# DA6.net
KiCad netlist of a schematic drawn in EAGLE
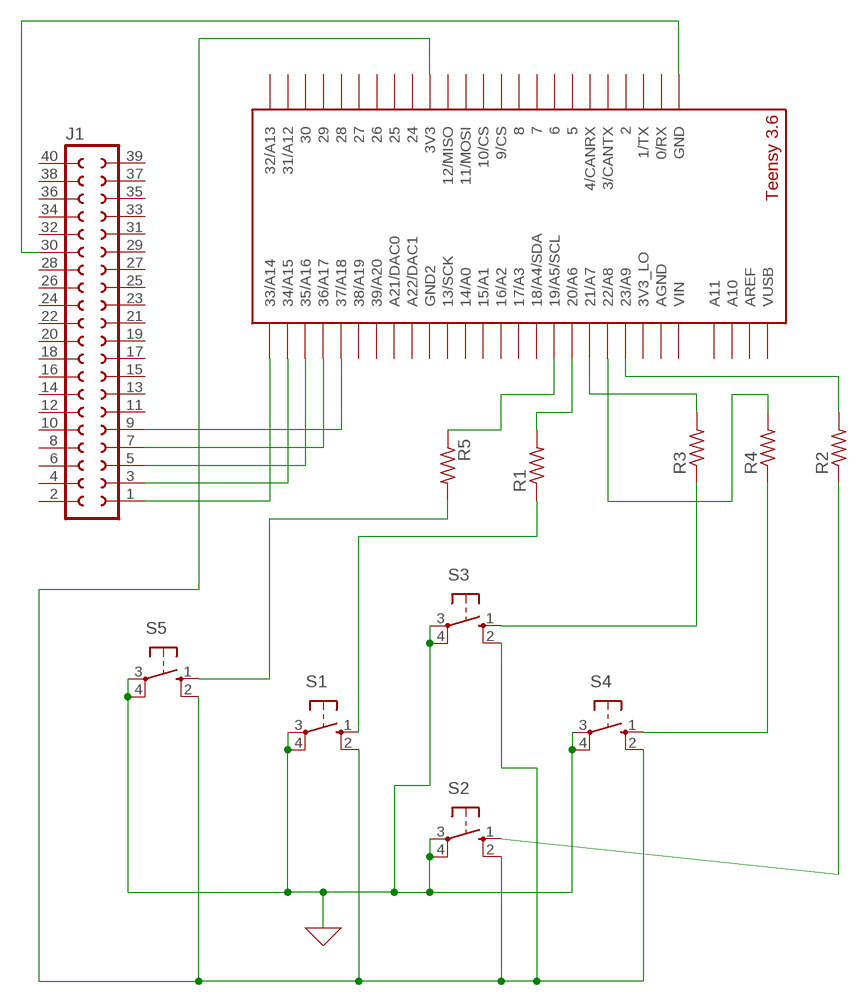
[diagram p0: schematic, sheet 1]

(export (version "E")
  (design (tool "Eeschema 10.0.6"))
  (components
    (comp (ref "J1")
      (value "SOCKET-40V")
      (footprint "eagle-import:S40V")
      (libsource (lib "eagle-import") (part "SOCKET-40V"))
    )
    (comp (ref "R1")
      (value "R-US_0204/2V")
      (footprint "eagle-import:0204V")
      (libsource (lib "eagle-import") (part "R-US_0204/2V"))
    )
    (comp (ref "R2")
      (value "R-US_0204/2V")
      (footprint "eagle-import:0204V")
      (libsource (lib "eagle-import") (part "R-US_0204/2V"))
    )
    (comp (ref "R3")
      (value "R-US_0204/2V")
      (footprint "eagle-import:0204V")
      (libsource (lib "eagle-import") (part "R-US_0204/2V"))
    )
    (comp (ref "R4")
      (value "R-US_0204/2V")
      (footprint "eagle-import:0204V")
      (libsource (lib "eagle-import") (part "R-US_0204/2V"))
    )
    (comp (ref "R5")
      (value "R-US_0204/2V")
      (footprint "eagle-import:0204V")
      (libsource (lib "eagle-import") (part "R-US_0204/2V"))
    )
    (comp (ref "S1")
      (value "10-XX")
      (footprint "eagle-import:B3F-10XX")
      (fields (field (name "MPN") "B3F-1000"))
      (libsource (lib "eagle-import") (part "10-XX"))
    )
    (comp (ref "S2")
      (value "10-XX")
      (footprint "eagle-import:B3F-10XX")
      (fields (field (name "MPN") "B3F-1000"))
      (libsource (lib "eagle-import") (part "10-XX"))
    )
    (comp (ref "S3")
      (value "10-XX")
      (footprint "eagle-import:B3F-10XX")
      (fields (field (name "MPN") "B3F-1000"))
      (libsource (lib "eagle-import") (part "10-XX"))
    )
    (comp (ref "S4")
      (value "10-XX")
      (footprint "eagle-import:B3F-10XX")
      (fields (field (name "MPN") "B3F-1000"))
      (libsource (lib "eagle-import") (part "10-XX"))
    )
    (comp (ref "S5")
      (value "10-XX")
      (footprint "eagle-import:B3F-10XX")
      (fields (field (name "MPN") "B3F-1000"))
      (libsource (lib "eagle-import") (part "10-XX"))
    )
    (comp (ref "U$1")
      (value "TEENSY_3.5/3.6_BASIC")
      (footprint "eagle-import:TEENSY_3.5_3.6_BASIC")
      (libsource (lib "eagle-import") (part "TEENSY_3.5/3.6_BASIC"))
    )
  )
  (nets
    (net (code "1") (name "GND") (class "Default")
      (node (ref "S1") (pin "3") (pinfunction "P_3") (pintype "passive"))
      (node (ref "S1") (pin "4") (pinfunction "P1_4") (pintype "passive"))
      (node (ref "S2") (pin "3") (pinfunction "P_3") (pintype "passive"))
      (node (ref "S2") (pin "4") (pinfunction "P1_4") (pintype "passive"))
      (node (ref "S3") (pin "3") (pinfunction "P_3") (pintype "passive"))
      (node (ref "S3") (pin "4") (pinfunction "P1_4") (pintype "passive"))
      (node (ref "S4") (pin "3") (pinfunction "P_3") (pintype "passive"))
      (node (ref "S4") (pin "4") (pinfunction "P1_4") (pintype "passive"))
      (node (ref "S5") (pin "3") (pinfunction "P_3") (pintype "passive"))
      (node (ref "S5") (pin "4") (pinfunction "P1_4") (pintype "passive"))
    )
    (net (code "2") (name "Net-(J1-Pad1)") (class "Default")
      (node (ref "J1") (pin "1") (pinfunction "1_1") (pintype "passive"))
      (node (ref "U$1") (pin "33/A14") (pinfunction "33/A14_33/A14") (pintype "bidirectional"))
    )
    (net (code "3") (name "Net-(J1-Pad3)") (class "Default")
      (node (ref "J1") (pin "3") (pinfunction "3_3") (pintype "passive"))
      (node (ref "U$1") (pin "34/A15") (pinfunction "34/A15_34/A15") (pintype "bidirectional"))
    )
    (net (code "4") (name "Net-(J1-Pad5)") (class "Default")
      (node (ref "J1") (pin "5") (pinfunction "5_5") (pintype "passive"))
      (node (ref "U$1") (pin "35/A16") (pinfunction "35/A16_35/A16") (pintype "bidirectional"))
    )
    (net (code "5") (name "Net-(J1-Pad7)") (class "Default")
      (node (ref "J1") (pin "7") (pinfunction "7_7") (pintype "passive"))
      (node (ref "U$1") (pin "36/A17") (pinfunction "36/A17_36/A17") (pintype "bidirectional"))
    )
    (net (code "6") (name "Net-(J1-Pad9)") (class "Default")
      (node (ref "J1") (pin "9") (pinfunction "9_9") (pintype "passive"))
      (node (ref "U$1") (pin "37/A18") (pinfunction "37/A18_37/A18") (pintype "bidirectional"))
    )
    (net (code "7") (name "Net-(J1-Pad30)") (class "Default")
      (node (ref "J1") (pin "30") (pinfunction "30_30") (pintype "passive"))
      (node (ref "U$1") (pin "GND") (pinfunction "GND_GND") (pintype "bidirectional"))
    )
    (net (code "8") (name "Net-(R1-Pad2)") (class "Default")
      (node (ref "R1") (pin "2") (pinfunction "2_2") (pintype "passive"))
      (node (ref "U$1") (pin "20/A6") (pinfunction "20/A6_20/A6") (pintype "bidirectional"))
    )
    (net (code "9") (name "Net-(R2-Pad2)") (class "Default")
      (node (ref "R2") (pin "2") (pinfunction "2_2") (pintype "passive"))
      (node (ref "U$1") (pin "23/A9") (pinfunction "23/A9_23/A9") (pintype "bidirectional"))
    )
    (net (code "10") (name "Net-(R3-Pad2)") (class "Default")
      (node (ref "R3") (pin "2") (pinfunction "2_2") (pintype "passive"))
      (node (ref "U$1") (pin "21/A7") (pinfunction "21/A7_21/A7") (pintype "bidirectional"))
    )
    (net (code "11") (name "Net-(R4-Pad2)") (class "Default")
      (node (ref "R4") (pin "2") (pinfunction "2_2") (pintype "passive"))
      (node (ref "U$1") (pin "22/A8") (pinfunction "22/A8_22/A8") (pintype "bidirectional"))
    )
    (net (code "12") (name "Net-(R5-Pad1)") (class "Default")
      (node (ref "R5") (pin "1") (pinfunction "1_1") (pintype "passive"))
      (node (ref "U$1") (pin "19/A5/SCL") (pinfunction "19/A5/SCL_19/A5/SCL") (pintype "bidirectional"))
    )
    (net (code "13") (name "Net-(S1-S)") (class "Default")
      (node (ref "R1") (pin "1") (pinfunction "1_1") (pintype "passive"))
      (node (ref "S1") (pin "1") (pinfunction "S_1") (pintype "passive"))
    )
    (net (code "14") (name "Net-(S1-S1)") (class "Default")
      (node (ref "S1") (pin "2") (pinfunction "S1_2") (pintype "passive"))
      (node (ref "S2") (pin "2") (pinfunction "S1_2") (pintype "passive"))
      (node (ref "S3") (pin "2") (pinfunction "S1_2") (pintype "passive"))
      (node (ref "S4") (pin "2") (pinfunction "S1_2") (pintype "passive"))
      (node (ref "S5") (pin "2") (pinfunction "S1_2") (pintype "passive"))
      (node (ref "U$1") (pin "3V3") (pinfunction "3V3_3V3") (pintype "bidirectional"))
    )
    (net (code "15") (name "Net-(S2-S)") (class "Default")
      (node (ref "R2") (pin "1") (pinfunction "1_1") (pintype "passive"))
      (node (ref "S2") (pin "1") (pinfunction "S_1") (pintype "passive"))
    )
    (net (code "16") (name "Net-(S3-S)") (class "Default")
      (node (ref "R3") (pin "1") (pinfunction "1_1") (pintype "passive"))
      (node (ref "S3") (pin "1") (pinfunction "S_1") (pintype "passive"))
    )
    (net (code "17") (name "Net-(S4-S)") (class "Default")
      (node (ref "R4") (pin "1") (pinfunction "1_1") (pintype "passive"))
      (node (ref "S4") (pin "1") (pinfunction "S_1") (pintype "passive"))
    )
    (net (code "18") (name "Net-(S5-S)") (class "Default")
      (node (ref "R5") (pin "2") (pinfunction "2_2") (pintype "passive"))
      (node (ref "S5") (pin "1") (pinfunction "S_1") (pintype "passive"))
    )
    (net (code "19") (name "unconnected-(J1-Pad2)") (class "Default")
      (node (ref "J1") (pin "2") (pinfunction "2_2") (pintype "passive"))
    )
    (net (code "20") (name "unconnected-(J1-Pad4)") (class "Default")
      (node (ref "J1") (pin "4") (pinfunction "4_4") (pintype "passive"))
    )
    (net (code "21") (name "unconnected-(J1-Pad6)") (class "Default")
      (node (ref "J1") (pin "6") (pinfunction "6_6") (pintype "passive"))
    )
    (net (code "22") (name "unconnected-(J1-Pad8)") (class "Default")
      (node (ref "J1") (pin "8") (pinfunction "8_8") (pintype "passive"))
    )
    (net (code "23") (name "unconnected-(J1-Pad10)") (class "Default")
      (node (ref "J1") (pin "10") (pinfunction "10_10") (pintype "passive"))
    )
    (net (code "24") (name "unconnected-(J1-Pad11)") (class "Default")
      (node (ref "J1") (pin "11") (pinfunction "11_11") (pintype "passive"))
    )
    (net (code "25") (name "unconnected-(J1-Pad12)") (class "Default")
      (node (ref "J1") (pin "12") (pinfunction "12_12") (pintype "passive"))
    )
    (net (code "26") (name "unconnected-(J1-Pad13)") (class "Default")
      (node (ref "J1") (pin "13") (pinfunction "13_13") (pintype "passive"))
    )
    (net (code "27") (name "unconnected-(J1-Pad14)") (class "Default")
      (node (ref "J1") (pin "14") (pinfunction "14_14") (pintype "passive"))
    )
    (net (code "28") (name "unconnected-(J1-Pad15)") (class "Default")
      (node (ref "J1") (pin "15") (pinfunction "15_15") (pintype "passive"))
    )
    (net (code "29") (name "unconnected-(J1-Pad16)") (class "Default")
      (node (ref "J1") (pin "16") (pinfunction "16_16") (pintype "passive"))
    )
    (net (code "30") (name "unconnected-(J1-Pad17)") (class "Default")
      (node (ref "J1") (pin "17") (pinfunction "17_17") (pintype "passive"))
    )
    (net (code "31") (name "unconnected-(J1-Pad18)") (class "Default")
      (node (ref "J1") (pin "18") (pinfunction "18_18") (pintype "passive"))
    )
    (net (code "32") (name "unconnected-(J1-Pad19)") (class "Default")
      (node (ref "J1") (pin "19") (pinfunction "19_19") (pintype "passive"))
    )
    (net (code "33") (name "unconnected-(J1-Pad20)") (class "Default")
      (node (ref "J1") (pin "20") (pinfunction "20_20") (pintype "passive"))
    )
    (net (code "34") (name "unconnected-(J1-Pad21)") (class "Default")
      (node (ref "J1") (pin "21") (pinfunction "21_21") (pintype "passive"))
    )
    (net (code "35") (name "unconnected-(J1-Pad22)") (class "Default")
      (node (ref "J1") (pin "22") (pinfunction "22_22") (pintype "passive"))
    )
    (net (code "36") (name "unconnected-(J1-Pad23)") (class "Default")
      (node (ref "J1") (pin "23") (pinfunction "23_23") (pintype "passive"))
    )
    (net (code "37") (name "unconnected-(J1-Pad24)") (class "Default")
      (node (ref "J1") (pin "24") (pinfunction "24_24") (pintype "passive"))
    )
    (net (code "38") (name "unconnected-(J1-Pad25)") (class "Default")
      (node (ref "J1") (pin "25") (pinfunction "25_25") (pintype "passive"))
    )
    (net (code "39") (name "unconnected-(J1-Pad26)") (class "Default")
      (node (ref "J1") (pin "26") (pinfunction "26_26") (pintype "passive"))
    )
    (net (code "40") (name "unconnected-(J1-Pad27)") (class "Default")
      (node (ref "J1") (pin "27") (pinfunction "27_27") (pintype "passive"))
    )
    (net (code "41") (name "unconnected-(J1-Pad28)") (class "Default")
      (node (ref "J1") (pin "28") (pinfunction "28_28") (pintype "passive"))
    )
    (net (code "42") (name "unconnected-(J1-Pad29)") (class "Default")
      (node (ref "J1") (pin "29") (pinfunction "29_29") (pintype "passive"))
    )
    (net (code "43") (name "unconnected-(J1-Pad31)") (class "Default")
      (node (ref "J1") (pin "31") (pinfunction "31_31") (pintype "passive"))
    )
    (net (code "44") (name "unconnected-(J1-Pad32)") (class "Default")
      (node (ref "J1") (pin "32") (pinfunction "32_32") (pintype "passive"))
    )
    (net (code "45") (name "unconnected-(J1-Pad33)") (class "Default")
      (node (ref "J1") (pin "33") (pinfunction "33_33") (pintype "passive"))
    )
    (net (code "46") (name "unconnected-(J1-Pad34)") (class "Default")
      (node (ref "J1") (pin "34") (pinfunction "34_34") (pintype "passive"))
    )
    (net (code "47") (name "unconnected-(J1-Pad35)") (class "Default")
      (node (ref "J1") (pin "35") (pinfunction "35_35") (pintype "passive"))
    )
    (net (code "48") (name "unconnected-(J1-Pad36)") (class "Default")
      (node (ref "J1") (pin "36") (pinfunction "36_36") (pintype "passive"))
    )
    (net (code "49") (name "unconnected-(J1-Pad37)") (class "Default")
      (node (ref "J1") (pin "37") (pinfunction "37_37") (pintype "passive"))
    )
    (net (code "50") (name "unconnected-(J1-Pad38)") (class "Default")
      (node (ref "J1") (pin "38") (pinfunction "38_38") (pintype "passive"))
    )
    (net (code "51") (name "unconnected-(J1-Pad39)") (class "Default")
      (node (ref "J1") (pin "39") (pinfunction "39_39") (pintype "passive"))
    )
    (net (code "52") (name "unconnected-(J1-Pad40)") (class "Default")
      (node (ref "J1") (pin "40") (pinfunction "40_40") (pintype "passive"))
    )
    (net (code "53") (name "unconnected-(U$1-A21{slash}DAC0-Pad21{slash}DAC0)") (class "Default")
      (node (ref "U$1") (pin "21/DAC0") (pinfunction "A21/DAC0_21/DAC0") (pintype "bidirectional"))
    )
    (net (code "54") (name "unconnected-(U$1-Pad0{slash}RX)") (class "Default")
      (node (ref "U$1") (pin "0/RX") (pinfunction "0/RX_0/RX") (pintype "bidirectional"))
    )
    (net (code "55") (name "unconnected-(U$1-Pad1{slash}TX)") (class "Default")
      (node (ref "U$1") (pin "1/TX") (pinfunction "1/TX_1/TX") (pintype "bidirectional"))
    )
    (net (code "56") (name "unconnected-(U$1-Pad2)") (class "Default")
      (node (ref "U$1") (pin "2") (pinfunction "2_2") (pintype "bidirectional"))
    )
    (net (code "57") (name "unconnected-(U$1-Pad3V3_LO)") (class "Default")
      (node (ref "U$1") (pin "3V3_LO") (pinfunction "3V3_LO_3V3_LO") (pintype "bidirectional"))
    )
    (net (code "58") (name "unconnected-(U$1-Pad3{slash}CANTX)") (class "Default")
      (node (ref "U$1") (pin "3/CANTX") (pinfunction "3/CANTX_3/CANTX") (pintype "bidirectional"))
    )
    (net (code "59") (name "unconnected-(U$1-Pad4{slash}CANRX)") (class "Default")
      (node (ref "U$1") (pin "4/CANRX") (pinfunction "4/CANRX_4/CANRX") (pintype "bidirectional"))
    )
    (net (code "60") (name "unconnected-(U$1-Pad5)") (class "Default")
      (node (ref "U$1") (pin "5") (pinfunction "5_5") (pintype "bidirectional"))
    )
    (net (code "61") (name "unconnected-(U$1-Pad6)") (class "Default")
      (node (ref "U$1") (pin "6") (pinfunction "6_6") (pintype "bidirectional"))
    )
    (net (code "62") (name "unconnected-(U$1-Pad7)") (class "Default")
      (node (ref "U$1") (pin "7") (pinfunction "7_7") (pintype "bidirectional"))
    )
    (net (code "63") (name "unconnected-(U$1-Pad8)") (class "Default")
      (node (ref "U$1") (pin "8") (pinfunction "8_8") (pintype "bidirectional"))
    )
    (net (code "64") (name "unconnected-(U$1-Pad9{slash}CS)") (class "Default")
      (node (ref "U$1") (pin "9/CS") (pinfunction "9/CS_9/CS") (pintype "bidirectional"))
    )
    (net (code "65") (name "unconnected-(U$1-Pad10{slash}CS)") (class "Default")
      (node (ref "U$1") (pin "10/CS") (pinfunction "10/CS_10/CS") (pintype "bidirectional"))
    )
    (net (code "66") (name "unconnected-(U$1-Pad11{slash}MOSI)") (class "Default")
      (node (ref "U$1") (pin "11/MOSI") (pinfunction "11/MOSI_11/MOSI") (pintype "bidirectional"))
    )
    (net (code "67") (name "unconnected-(U$1-Pad12{slash}MISO)") (class "Default")
      (node (ref "U$1") (pin "12/MISO") (pinfunction "12/MISO_12/MISO") (pintype "bidirectional"))
    )
    (net (code "68") (name "unconnected-(U$1-Pad13{slash}SCK)") (class "Default")
      (node (ref "U$1") (pin "13/SCK") (pinfunction "13/SCK_13/SCK") (pintype "bidirectional"))
    )
    (net (code "69") (name "unconnected-(U$1-Pad14{slash}A0)") (class "Default")
      (node (ref "U$1") (pin "14/A0") (pinfunction "14/A0_14/A0") (pintype "bidirectional"))
    )
    (net (code "70") (name "unconnected-(U$1-Pad15{slash}A1)") (class "Default")
      (node (ref "U$1") (pin "15/A1") (pinfunction "15/A1_15/A1") (pintype "bidirectional"))
    )
    (net (code "71") (name "unconnected-(U$1-Pad16{slash}A2)") (class "Default")
      (node (ref "U$1") (pin "16/A2") (pinfunction "16/A2_16/A2") (pintype "bidirectional"))
    )
    (net (code "72") (name "unconnected-(U$1-Pad17{slash}A3)") (class "Default")
      (node (ref "U$1") (pin "17/A3") (pinfunction "17/A3_17/A3") (pintype "bidirectional"))
    )
    (net (code "73") (name "unconnected-(U$1-Pad18{slash}A4{slash}SDA)") (class "Default")
      (node (ref "U$1") (pin "18/A4/SDA") (pinfunction "18/A4/SDA_18/A4/SDA") (pintype "bidirectional"))
    )
    (net (code "74") (name "unconnected-(U$1-Pad24)") (class "Default")
      (node (ref "U$1") (pin "24") (pinfunction "24_24") (pintype "bidirectional"))
    )
    (net (code "75") (name "unconnected-(U$1-Pad25)") (class "Default")
      (node (ref "U$1") (pin "25") (pinfunction "25_25") (pintype "bidirectional"))
    )
    (net (code "76") (name "unconnected-(U$1-Pad26)") (class "Default")
      (node (ref "U$1") (pin "26") (pinfunction "26_26") (pintype "bidirectional"))
    )
    (net (code "77") (name "unconnected-(U$1-Pad27)") (class "Default")
      (node (ref "U$1") (pin "27") (pinfunction "27_27") (pintype "bidirectional"))
    )
    (net (code "78") (name "unconnected-(U$1-Pad28)") (class "Default")
      (node (ref "U$1") (pin "28") (pinfunction "28_28") (pintype "bidirectional"))
    )
    (net (code "79") (name "unconnected-(U$1-Pad29)") (class "Default")
      (node (ref "U$1") (pin "29") (pinfunction "29_29") (pintype "bidirectional"))
    )
    (net (code "80") (name "unconnected-(U$1-Pad30)") (class "Default")
      (node (ref "U$1") (pin "30") (pinfunction "30_30") (pintype "bidirectional"))
    )
    (net (code "81") (name "unconnected-(U$1-Pad31{slash}A12)") (class "Default")
      (node (ref "U$1") (pin "31/A12") (pinfunction "31/A12_31/A12") (pintype "bidirectional"))
    )
    (net (code "82") (name "unconnected-(U$1-Pad32{slash}A13)") (class "Default")
      (node (ref "U$1") (pin "32/A13") (pinfunction "32/A13_32/A13") (pintype "bidirectional"))
    )
    (net (code "83") (name "unconnected-(U$1-Pad38{slash}A19)") (class "Default")
      (node (ref "U$1") (pin "38/A19") (pinfunction "38/A19_38/A19") (pintype "bidirectional"))
    )
    (net (code "84") (name "unconnected-(U$1-Pad39{slash}A20)") (class "Default")
      (node (ref "U$1") (pin "39/A20") (pinfunction "39/A20_39/A20") (pintype "bidirectional"))
    )
    (net (code "85") (name "unconnected-(U$1-PadA10)") (class "Default")
      (node (ref "U$1") (pin "A10") (pinfunction "A10_A10") (pintype "bidirectional"))
    )
    (net (code "86") (name "unconnected-(U$1-PadA11)") (class "Default")
      (node (ref "U$1") (pin "A11") (pinfunction "A11_A11") (pintype "bidirectional"))
    )
    (net (code "87") (name "unconnected-(U$1-PadA22{slash}DAC1)") (class "Default")
      (node (ref "U$1") (pin "A22/DAC1") (pinfunction "A22/DAC1_A22/DAC1") (pintype "bidirectional"))
    )
    (net (code "88") (name "unconnected-(U$1-PadAGND)") (class "Default")
      (node (ref "U$1") (pin "AGND") (pinfunction "AGND_AGND") (pintype "bidirectional"))
    )
    (net (code "89") (name "unconnected-(U$1-PadAREF)") (class "Default")
      (node (ref "U$1") (pin "AREF") (pinfunction "AREF_AREF") (pintype "bidirectional"))
    )
    (net (code "90") (name "unconnected-(U$1-PadGND2)") (class "Default")
      (node (ref "U$1") (pin "GND2") (pinfunction "GND2_GND2") (pintype "bidirectional"))
    )
    (net (code "91") (name "unconnected-(U$1-PadVIN)") (class "Default")
      (node (ref "U$1") (pin "VIN") (pinfunction "VIN_VIN") (pintype "bidirectional"))
    )
    (net (code "92") (name "unconnected-(U$1-PadVUSB)") (class "Default")
      (node (ref "U$1") (pin "VUSB") (pinfunction "VUSB_VUSB") (pintype "bidirectional"))
    )
  )
)
